# lithium.net
KiCad netlist of a schematic drawn in EAGLE
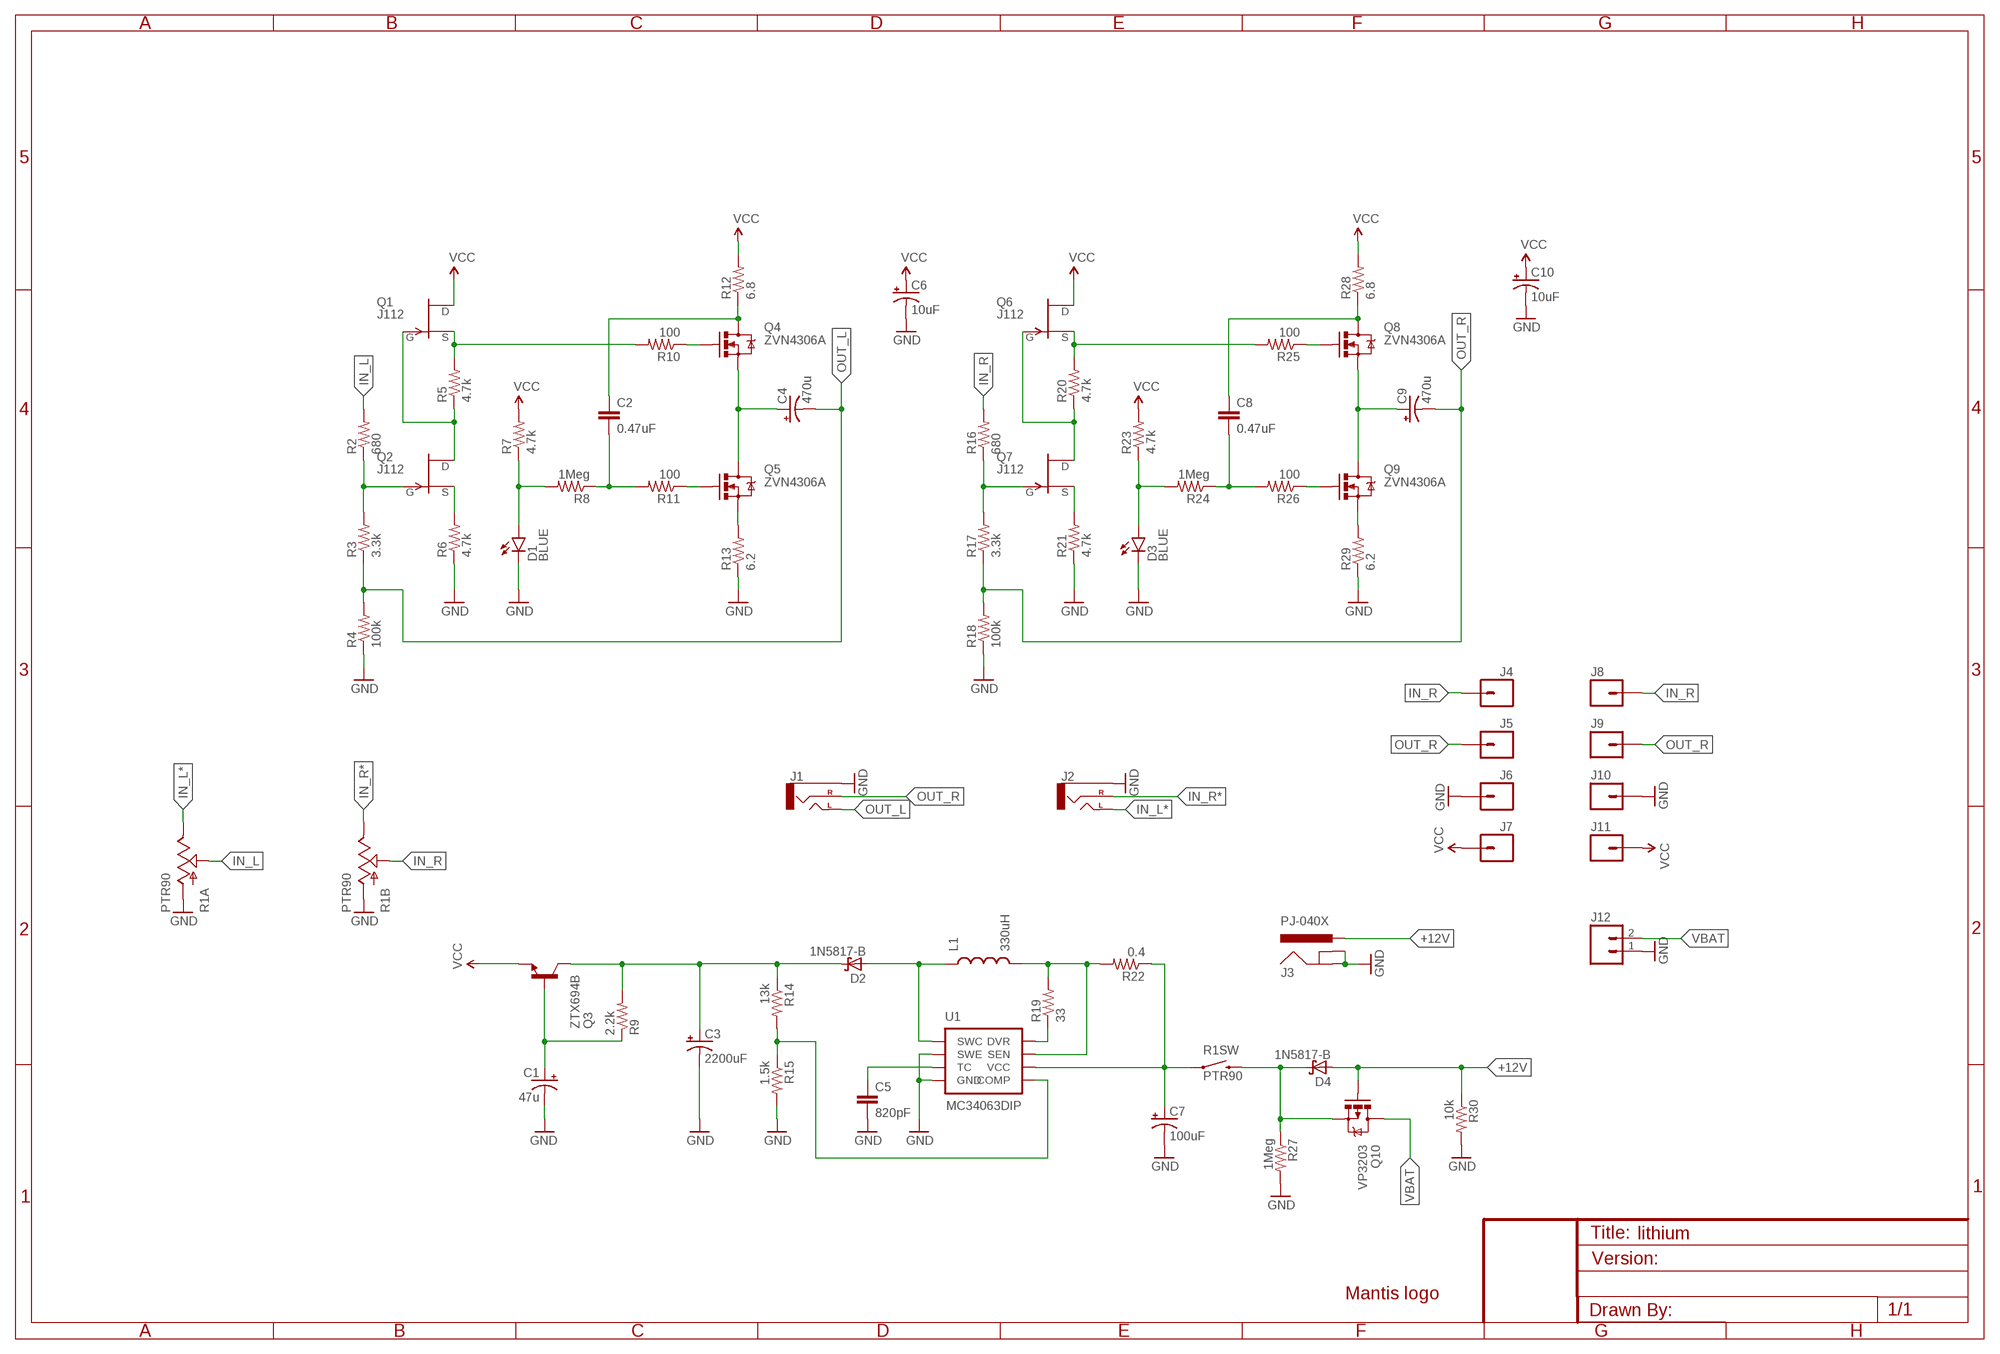
[diagram p0: schematic, sheet 1]

(export (version "E")
  (design (tool "Eeschema 10.0.6"))
  (components
    (comp (ref "C1")
      (value "47u")
      (footprint "eagle-import:CPOL-RADIAL-10UF-25V-SM")
      (libsource (lib "eagle-import") (part "CAP_POLPTH1-SM"))
    )
    (comp (ref "C2")
      (value "0.47uF")
      (footprint "eagle-import:C5B3.5")
      (libsource (lib "eagle-import") (part "C5/3.5"))
    )
    (comp (ref "C3")
      (value "2200uF")
      (footprint "eagle-import:CPOL-RADIAL-1000UF-25V")
      (libsource (lib "eagle-import") (part "CAP_POLPTH4"))
    )
    (comp (ref "C4")
      (value "470u")
      (footprint "eagle-import:CPOL-RADIAL-8_3.5")
      (libsource (lib "eagle-import") (part "CAP_POLPTH8MM"))
    )
    (comp (ref "C5")
      (value "820pF")
      (footprint "eagle-import:CAP-PTH-SMALL")
      (libsource (lib "eagle-import") (part "CAPPTH"))
    )
    (comp (ref "C6")
      (value "10uF")
      (footprint "eagle-import:CPOL-RADIAL-10UF-25V-SM")
      (libsource (lib "eagle-import") (part "CAP_POLPTH1-SM"))
    )
    (comp (ref "C7")
      (value "100uF")
      (footprint "eagle-import:CPOL-RADIAL-100UF-25V")
      (libsource (lib "eagle-import") (part "CAP_POLPTH1"))
    )
    (comp (ref "C8")
      (value "0.47uF")
      (footprint "eagle-import:C5B3.5")
      (libsource (lib "eagle-import") (part "C5/3.5"))
    )
    (comp (ref "C9")
      (value "470u")
      (footprint "eagle-import:CPOL-RADIAL-8_3.5")
      (libsource (lib "eagle-import") (part "CAP_POLPTH8MM"))
    )
    (comp (ref "C10")
      (value "10uF")
      (footprint "eagle-import:CPOL-RADIAL-10UF-25V-SM")
      (libsource (lib "eagle-import") (part "CAP_POLPTH1-SM"))
    )
    (comp (ref "D1")
      (value "BLUE")
      (footprint "eagle-import:LED3MM-SM")
      (libsource (lib "eagle-import") (part "LED3MM-SM"))
    )
    (comp (ref "D2")
      (value "1N5817-B")
      (footprint "eagle-import:DO41-7.6")
      (libsource (lib "eagle-import") (part "1N5817-B"))
    )
    (comp (ref "D3")
      (value "BLUE")
      (footprint "eagle-import:LED3MM-SM")
      (libsource (lib "eagle-import") (part "LED3MM-SM"))
    )
    (comp (ref "D4")
      (value "1N5817-B")
      (footprint "eagle-import:DO41-7.6")
      (libsource (lib "eagle-import") (part "1N5817-B"))
    )
    (comp (ref "J1")
      (value "AUDIO-JACKPTH")
      (footprint "eagle-import:AUDIO-JACK")
      (libsource (lib "eagle-import") (part "AUDIO-JACKPTH"))
    )
    (comp (ref "J2")
      (value "AUDIO-JACKPTH")
      (footprint "eagle-import:AUDIO-JACK")
      (libsource (lib "eagle-import") (part "AUDIO-JACKPTH"))
    )
    (comp (ref "J3")
      (value "PJ-040X")
      (footprint "eagle-import:PJ-040X")
      (libsource (lib "eagle-import") (part "PJ-040X"))
    )
    (comp (ref "J4")
      (value "M01PTH")
      (footprint "eagle-import:1X01")
      (libsource (lib "eagle-import") (part "M01PTH"))
    )
    (comp (ref "J5")
      (value "M01PTH")
      (footprint "eagle-import:1X01")
      (libsource (lib "eagle-import") (part "M01PTH"))
    )
    (comp (ref "J6")
      (value "M01PTH")
      (footprint "eagle-import:1X01")
      (libsource (lib "eagle-import") (part "M01PTH"))
    )
    (comp (ref "J7")
      (value "M01PTH")
      (footprint "eagle-import:1X01")
      (libsource (lib "eagle-import") (part "M01PTH"))
    )
    (comp (ref "J8")
      (value "M01PTH")
      (footprint "eagle-import:1X01")
      (libsource (lib "eagle-import") (part "M01PTH"))
    )
    (comp (ref "J9")
      (value "M01PTH")
      (footprint "eagle-import:1X01")
      (libsource (lib "eagle-import") (part "M01PTH"))
    )
    (comp (ref "J10")
      (value "M01PTH")
      (footprint "eagle-import:1X01")
      (libsource (lib "eagle-import") (part "M01PTH"))
    )
    (comp (ref "J11")
      (value "M01PTH")
      (footprint "eagle-import:1X01")
      (libsource (lib "eagle-import") (part "M01PTH"))
    )
    (comp (ref "J12")
      (value "M02PTH")
      (footprint "eagle-import:1X02")
      (libsource (lib "eagle-import") (part "M02PTH"))
    )
    (comp (ref "L1")
      (value "330uH")
      (footprint "eagle-import:RLB0912")
      (libsource (lib "eagle-import") (part "INDUCTORRLB0912"))
    )
    (comp (ref "LOGO1")
      (value "LOGO-MANTIS")
      (footprint "eagle-import:LOGO-MANTIS")
      (libsource (lib "eagle-import") (part "LOGO-MANTIS"))
    )
    (comp (ref "Q1")
      (value "J112")
      (footprint "eagle-import:TO-92")
      (libsource (lib "eagle-import") (part "J112"))
    )
    (comp (ref "Q2")
      (value "J112")
      (footprint "eagle-import:TO-92")
      (libsource (lib "eagle-import") (part "J112"))
    )
    (comp (ref "Q3")
      (value "ZTX694B")
      (footprint "eagle-import:TO-92")
      (libsource (lib "eagle-import") (part "ZTX694B"))
    )
    (comp (ref "Q4")
      (value "ZVN4306A")
      (footprint "eagle-import:TO-92")
      (libsource (lib "eagle-import") (part "ZVN4306A"))
    )
    (comp (ref "Q5")
      (value "ZVN4306A")
      (footprint "eagle-import:TO-92")
      (libsource (lib "eagle-import") (part "ZVN4306A"))
    )
    (comp (ref "Q6")
      (value "J112")
      (footprint "eagle-import:TO-92")
      (libsource (lib "eagle-import") (part "J112"))
    )
    (comp (ref "Q7")
      (value "J112")
      (footprint "eagle-import:TO-92")
      (libsource (lib "eagle-import") (part "J112"))
    )
    (comp (ref "Q8")
      (value "ZVN4306A")
      (footprint "eagle-import:TO-92")
      (libsource (lib "eagle-import") (part "ZVN4306A"))
    )
    (comp (ref "Q9")
      (value "ZVN4306A")
      (footprint "eagle-import:TO-92")
      (libsource (lib "eagle-import") (part "ZVN4306A"))
    )
    (comp (ref "Q10")
      (value "VP3203")
      (footprint "eagle-import:TO-92")
      (libsource (lib "eagle-import") (part "VP3203"))
    )
    (comp (ref "R1")
      (value "PTR90")
      (footprint "eagle-import:PTR902")
      (libsource (lib "eagle-import") (part "PTR90"))
    )
    (comp (ref "R2")
      (value "680")
      (footprint "eagle-import:AXIAL-0.4-SM")
      (libsource (lib "eagle-import") (part "RESISTORPTH-1/4W-SM"))
    )
    (comp (ref "R3")
      (value "3.3k")
      (footprint "eagle-import:AXIAL-0.4-SM")
      (libsource (lib "eagle-import") (part "RESISTORPTH-1/4W-SM"))
    )
    (comp (ref "R4")
      (value "100k")
      (footprint "eagle-import:AXIAL-0.4-SM")
      (libsource (lib "eagle-import") (part "RESISTORPTH-1/4W-SM"))
    )
    (comp (ref "R5")
      (value "4.7k")
      (footprint "eagle-import:AXIAL-0.4-SM")
      (libsource (lib "eagle-import") (part "RESISTORPTH-1/4W-SM"))
    )
    (comp (ref "R6")
      (value "4.7k")
      (footprint "eagle-import:AXIAL-0.4-SM")
      (libsource (lib "eagle-import") (part "RESISTORPTH-1/4W-SM"))
    )
    (comp (ref "R7")
      (value "4.7k")
      (footprint "eagle-import:AXIAL-0.4-SM")
      (libsource (lib "eagle-import") (part "RESISTORPTH-1/4W-SM"))
    )
    (comp (ref "R8")
      (value "1Meg")
      (footprint "eagle-import:AXIAL-0.4-SM")
      (libsource (lib "eagle-import") (part "RESISTORPTH-1/4W-SM"))
    )
    (comp (ref "R9")
      (value "2.2k")
      (footprint "eagle-import:AXIAL-0.4-SM")
      (libsource (lib "eagle-import") (part "RESISTORPTH-1/4W-SM"))
    )
    (comp (ref "R10")
      (value "100")
      (footprint "eagle-import:AXIAL-0.4-SM")
      (libsource (lib "eagle-import") (part "RESISTORPTH-1/4W-SM"))
    )
    (comp (ref "R11")
      (value "100")
      (footprint "eagle-import:AXIAL-0.4-SM")
      (libsource (lib "eagle-import") (part "RESISTORPTH-1/4W-SM"))
    )
    (comp (ref "R12")
      (value "6.8")
      (footprint "eagle-import:AXIAL-0.4-SM")
      (libsource (lib "eagle-import") (part "RESISTORPTH-1/4W-SM"))
    )
    (comp (ref "R13")
      (value "6.2")
      (footprint "eagle-import:AXIAL-0.4-SM")
      (libsource (lib "eagle-import") (part "RESISTORPTH-1/4W-SM"))
    )
    (comp (ref "R14")
      (value "13k")
      (footprint "eagle-import:AXIAL-0.4-SM")
      (libsource (lib "eagle-import") (part "RESISTORPTH-1/4W-SM"))
    )
    (comp (ref "R15")
      (value "1.5k")
      (footprint "eagle-import:AXIAL-0.4-SM")
      (libsource (lib "eagle-import") (part "RESISTORPTH-1/4W-SM"))
    )
    (comp (ref "R16")
      (value "680")
      (footprint "eagle-import:AXIAL-0.4-SM")
      (libsource (lib "eagle-import") (part "RESISTORPTH-1/4W-SM"))
    )
    (comp (ref "R17")
      (value "3.3k")
      (footprint "eagle-import:AXIAL-0.4-SM")
      (libsource (lib "eagle-import") (part "RESISTORPTH-1/4W-SM"))
    )
    (comp (ref "R18")
      (value "100k")
      (footprint "eagle-import:AXIAL-0.4-SM")
      (libsource (lib "eagle-import") (part "RESISTORPTH-1/4W-SM"))
    )
    (comp (ref "R19")
      (value "33")
      (footprint "eagle-import:AXIAL-0.4-SM")
      (libsource (lib "eagle-import") (part "RESISTORPTH-1/4W-SM"))
    )
    (comp (ref "R20")
      (value "4.7k")
      (footprint "eagle-import:AXIAL-0.4-SM")
      (libsource (lib "eagle-import") (part "RESISTORPTH-1/4W-SM"))
    )
    (comp (ref "R21")
      (value "4.7k")
      (footprint "eagle-import:AXIAL-0.4-SM")
      (libsource (lib "eagle-import") (part "RESISTORPTH-1/4W-SM"))
    )
    (comp (ref "R22")
      (value "0.4")
      (footprint "eagle-import:AXIAL-0.4-SM")
      (libsource (lib "eagle-import") (part "RESISTORPTH-1/4W-SM"))
    )
    (comp (ref "R23")
      (value "4.7k")
      (footprint "eagle-import:AXIAL-0.4-SM")
      (libsource (lib "eagle-import") (part "RESISTORPTH-1/4W-SM"))
    )
    (comp (ref "R24")
      (value "1Meg")
      (footprint "eagle-import:AXIAL-0.4-SM")
      (libsource (lib "eagle-import") (part "RESISTORPTH-1/4W-SM"))
    )
    (comp (ref "R25")
      (value "100")
      (footprint "eagle-import:AXIAL-0.4-SM")
      (libsource (lib "eagle-import") (part "RESISTORPTH-1/4W-SM"))
    )
    (comp (ref "R26")
      (value "100")
      (footprint "eagle-import:AXIAL-0.4-SM")
      (libsource (lib "eagle-import") (part "RESISTORPTH-1/4W-SM"))
    )
    (comp (ref "R27")
      (value "1Meg")
      (footprint "eagle-import:AXIAL-0.4-SM")
      (libsource (lib "eagle-import") (part "RESISTORPTH-1/4W-SM"))
    )
    (comp (ref "R28")
      (value "6.8")
      (footprint "eagle-import:AXIAL-0.4-SM")
      (libsource (lib "eagle-import") (part "RESISTORPTH-1/4W-SM"))
    )
    (comp (ref "R29")
      (value "6.2")
      (footprint "eagle-import:AXIAL-0.4-SM")
      (libsource (lib "eagle-import") (part "RESISTORPTH-1/4W-SM"))
    )
    (comp (ref "R30")
      (value "10k")
      (footprint "eagle-import:AXIAL-0.4-SM")
      (libsource (lib "eagle-import") (part "RESISTORPTH-1/4W-SM"))
    )
    (comp (ref "U1")
      (value "MC34063DIP")
      (footprint "eagle-import:DIP-08")
      (libsource (lib "eagle-import") (part "MC34063DIP"))
    )
  )
  (nets
    (net (code "1") (name "+12V") (class "Default")
      (node (ref "D4") (pin "A") (pinfunction "A_A") (pintype "passive"))
      (node (ref "J3") (pin "1") (pinfunction "PWR_1") (pintype "bidirectional"))
      (node (ref "Q10") (pin "2") (pinfunction "G_2") (pintype "passive"))
      (node (ref "R30") (pin "P$1") (pinfunction "1_P$1") (pintype "passive"))
    )
    (net (code "2") (name "GND") (class "Default")
      (node (ref "C1") (pin "2") (pinfunction "-_2") (pintype "passive"))
      (node (ref "C10") (pin "2") (pinfunction "-_2") (pintype "passive"))
      (node (ref "C3") (pin "-") (pinfunction "-_-") (pintype "passive"))
      (node (ref "C5") (pin "2") (pinfunction "2_2") (pintype "passive"))
      (node (ref "C6") (pin "2") (pinfunction "-_2") (pintype "passive"))
      (node (ref "C7") (pin "2") (pinfunction "-_2") (pintype "passive"))
      (node (ref "D1") (pin "K") (pinfunction "C_K") (pintype "passive"))
      (node (ref "D3") (pin "K") (pinfunction "C_K") (pintype "passive"))
      (node (ref "J1") (pin "SLEEVE") (pinfunction "SLEEVE_SLEEVE") (pintype "bidirectional"))
      (node (ref "J10") (pin "1") (pinfunction "1_1") (pintype "passive"))
      (node (ref "J12") (pin "1") (pinfunction "1_1") (pintype "passive"))
      (node (ref "J2") (pin "SLEEVE") (pinfunction "SLEEVE_SLEEVE") (pintype "bidirectional"))
      (node (ref "J3") (pin "2") (pinfunction "GND_2") (pintype "bidirectional"))
      (node (ref "J3") (pin "3") (pinfunction "GNDBREAK_3") (pintype "bidirectional"))
      (node (ref "J6") (pin "1") (pinfunction "1_1") (pintype "passive"))
      (node (ref "R1") (pin "R1.1") (pinfunction "A_R1.1") (pintype "passive"))
      (node (ref "R1") (pin "R2.1") (pinfunction "A_R2.1") (pintype "passive"))
      (node (ref "R13") (pin "P$1") (pinfunction "1_P$1") (pintype "passive"))
      (node (ref "R15") (pin "P$2") (pinfunction "2_P$2") (pintype "passive"))
      (node (ref "R18") (pin "P$1") (pinfunction "1_P$1") (pintype "passive"))
      (node (ref "R21") (pin "P$1") (pinfunction "1_P$1") (pintype "passive"))
      (node (ref "R27") (pin "P$2") (pinfunction "2_P$2") (pintype "passive"))
      (node (ref "R29") (pin "P$1") (pinfunction "1_P$1") (pintype "passive"))
      (node (ref "R30") (pin "P$2") (pinfunction "2_P$2") (pintype "passive"))
      (node (ref "R4") (pin "P$1") (pinfunction "1_P$1") (pintype "passive"))
      (node (ref "R6") (pin "P$1") (pinfunction "1_P$1") (pintype "passive"))
      (node (ref "U1") (pin "2") (pinfunction "SWE_2") (pintype "bidirectional"))
      (node (ref "U1") (pin "4") (pinfunction "GND_4") (pintype "bidirectional"))
    )
    (net (code "3") (name "IN_L") (class "Default")
      (node (ref "R1") (pin "R1.2") (pinfunction "S_R1.2") (pintype "passive"))
      (node (ref "R2") (pin "P$2") (pinfunction "2_P$2") (pintype "passive"))
    )
    (net (code "4") (name "IN_L*") (class "Default")
      (node (ref "J2") (pin "TIP") (pinfunction "LEFT_TIP") (pintype "bidirectional"))
      (node (ref "R1") (pin "R1.3") (pinfunction "E_R1.3") (pintype "passive"))
    )
    (net (code "5") (name "IN_R") (class "Default")
      (node (ref "J4") (pin "1") (pinfunction "1_1") (pintype "passive"))
      (node (ref "J8") (pin "1") (pinfunction "1_1") (pintype "passive"))
      (node (ref "R1") (pin "R2.2") (pinfunction "S_R2.2") (pintype "passive"))
      (node (ref "R16") (pin "P$2") (pinfunction "2_P$2") (pintype "passive"))
    )
    (net (code "6") (name "IN_R*") (class "Default")
      (node (ref "J2") (pin "RING") (pinfunction "RIGHT_RING") (pintype "bidirectional"))
      (node (ref "R1") (pin "R2.3") (pinfunction "E_R2.3") (pintype "passive"))
    )
    (net (code "7") (name "Net-(C1-+)") (class "Default")
      (node (ref "C1") (pin "1") (pinfunction "+_1") (pintype "passive"))
      (node (ref "Q3") (pin "2") (pinfunction "B_2") (pintype "passive"))
      (node (ref "R9") (pin "P$1") (pinfunction "1_P$1") (pintype "passive"))
    )
    (net (code "8") (name "Net-(C4-+)") (class "Default")
      (node (ref "C4") (pin "1") (pinfunction "+_1") (pintype "passive"))
      (node (ref "Q4") (pin "1") (pinfunction "S_1") (pintype "passive"))
      (node (ref "Q5") (pin "3") (pinfunction "D_3") (pintype "passive"))
    )
    (net (code "9") (name "Net-(C7-+)") (class "Default")
      (node (ref "C7") (pin "1") (pinfunction "+_1") (pintype "passive"))
      (node (ref "R1") (pin "SW1") (pinfunction "1_SW1") (pintype "passive"))
      (node (ref "R22") (pin "P$1") (pinfunction "1_P$1") (pintype "passive"))
      (node (ref "U1") (pin "6") (pinfunction "VCC_6") (pintype "bidirectional"))
    )
    (net (code "10") (name "Net-(C9-+)") (class "Default")
      (node (ref "C9") (pin "1") (pinfunction "+_1") (pintype "passive"))
      (node (ref "Q8") (pin "1") (pinfunction "S_1") (pintype "passive"))
      (node (ref "Q9") (pin "3") (pinfunction "D_3") (pintype "passive"))
    )
    (net (code "11") (name "Net-(Q1-G)") (class "Default")
      (node (ref "Q1") (pin "3") (pinfunction "G_3") (pintype "passive"))
      (node (ref "Q2") (pin "1") (pinfunction "D_1") (pintype "passive"))
      (node (ref "R5") (pin "P$1") (pinfunction "1_P$1") (pintype "passive"))
    )
    (net (code "12") (name "Net-(Q1-S)") (class "Default")
      (node (ref "Q1") (pin "2") (pinfunction "S_2") (pintype "passive"))
      (node (ref "R10") (pin "P$2") (pinfunction "2_P$2") (pintype "passive"))
      (node (ref "R5") (pin "P$2") (pinfunction "2_P$2") (pintype "passive"))
    )
    (net (code "13") (name "Net-(Q2-G)") (class "Default")
      (node (ref "Q2") (pin "3") (pinfunction "G_3") (pintype "passive"))
      (node (ref "R2") (pin "P$1") (pinfunction "1_P$1") (pintype "passive"))
      (node (ref "R3") (pin "P$2") (pinfunction "2_P$2") (pintype "passive"))
    )
    (net (code "14") (name "Net-(Q2-S)") (class "Default")
      (node (ref "Q2") (pin "2") (pinfunction "S_2") (pintype "passive"))
      (node (ref "R6") (pin "P$2") (pinfunction "2_P$2") (pintype "passive"))
    )
    (net (code "15") (name "Net-(Q3-C)") (class "Default")
      (node (ref "C3") (pin "+") (pinfunction "+_+") (pintype "passive"))
      (node (ref "D2") (pin "C") (pinfunction "C_C") (pintype "passive"))
      (node (ref "Q3") (pin "3") (pinfunction "C_3") (pintype "passive"))
      (node (ref "R14") (pin "P$1") (pinfunction "1_P$1") (pintype "passive"))
      (node (ref "R9") (pin "P$2") (pinfunction "2_P$2") (pintype "passive"))
    )
    (net (code "16") (name "Net-(Q4-D)") (class "Default")
      (node (ref "C2") (pin "1") (pinfunction "1_1") (pintype "passive"))
      (node (ref "Q4") (pin "3") (pinfunction "D_3") (pintype "passive"))
      (node (ref "R12") (pin "P$1") (pinfunction "1_P$1") (pintype "passive"))
    )
    (net (code "17") (name "Net-(Q4-G)") (class "Default")
      (node (ref "Q4") (pin "2") (pinfunction "G_2") (pintype "passive"))
      (node (ref "R10") (pin "P$1") (pinfunction "1_P$1") (pintype "passive"))
    )
    (net (code "18") (name "Net-(Q5-G)") (class "Default")
      (node (ref "Q5") (pin "2") (pinfunction "G_2") (pintype "passive"))
      (node (ref "R11") (pin "P$1") (pinfunction "1_P$1") (pintype "passive"))
    )
    (net (code "19") (name "Net-(Q5-S)") (class "Default")
      (node (ref "Q5") (pin "1") (pinfunction "S_1") (pintype "passive"))
      (node (ref "R13") (pin "P$2") (pinfunction "2_P$2") (pintype "passive"))
    )
    (net (code "20") (name "Net-(Q6-G)") (class "Default")
      (node (ref "Q6") (pin "3") (pinfunction "G_3") (pintype "passive"))
      (node (ref "Q7") (pin "1") (pinfunction "D_1") (pintype "passive"))
      (node (ref "R20") (pin "P$1") (pinfunction "1_P$1") (pintype "passive"))
    )
    (net (code "21") (name "Net-(Q6-S)") (class "Default")
      (node (ref "Q6") (pin "2") (pinfunction "S_2") (pintype "passive"))
      (node (ref "R20") (pin "P$2") (pinfunction "2_P$2") (pintype "passive"))
      (node (ref "R25") (pin "P$2") (pinfunction "2_P$2") (pintype "passive"))
    )
    (net (code "22") (name "Net-(Q7-G)") (class "Default")
      (node (ref "Q7") (pin "3") (pinfunction "G_3") (pintype "passive"))
      (node (ref "R16") (pin "P$1") (pinfunction "1_P$1") (pintype "passive"))
      (node (ref "R17") (pin "P$2") (pinfunction "2_P$2") (pintype "passive"))
    )
    (net (code "23") (name "Net-(Q7-S)") (class "Default")
      (node (ref "Q7") (pin "2") (pinfunction "S_2") (pintype "passive"))
      (node (ref "R21") (pin "P$2") (pinfunction "2_P$2") (pintype "passive"))
    )
    (net (code "24") (name "Net-(Q8-D)") (class "Default")
      (node (ref "C8") (pin "1") (pinfunction "1_1") (pintype "passive"))
      (node (ref "Q8") (pin "3") (pinfunction "D_3") (pintype "passive"))
      (node (ref "R28") (pin "P$1") (pinfunction "1_P$1") (pintype "passive"))
    )
    (net (code "25") (name "Net-(Q8-G)") (class "Default")
      (node (ref "Q8") (pin "2") (pinfunction "G_2") (pintype "passive"))
      (node (ref "R25") (pin "P$1") (pinfunction "1_P$1") (pintype "passive"))
    )
    (net (code "26") (name "Net-(Q9-G)") (class "Default")
      (node (ref "Q9") (pin "2") (pinfunction "G_2") (pintype "passive"))
      (node (ref "R26") (pin "P$1") (pinfunction "1_P$1") (pintype "passive"))
    )
    (net (code "27") (name "Net-(Q9-S)") (class "Default")
      (node (ref "Q9") (pin "1") (pinfunction "S_1") (pintype "passive"))
      (node (ref "R29") (pin "P$2") (pinfunction "2_P$2") (pintype "passive"))
    )
    (net (code "28") (name "Net-(Q10-S)") (class "Default")
      (node (ref "D4") (pin "C") (pinfunction "C_C") (pintype "passive"))
      (node (ref "Q10") (pin "1") (pinfunction "S_1") (pintype "passive"))
      (node (ref "R1") (pin "SW2") (pinfunction "2_SW2") (pintype "passive"))
      (node (ref "R27") (pin "P$1") (pinfunction "1_P$1") (pintype "passive"))
    )
    (net (code "29") (name "Net-(R7-1)") (class "Default")
      (node (ref "D1") (pin "A") (pinfunction "A_A") (pintype "passive"))
      (node (ref "R7") (pin "P$1") (pinfunction "1_P$1") (pintype "passive"))
      (node (ref "R8") (pin "P$2") (pinfunction "2_P$2") (pintype "passive"))
    )
    (net (code "30") (name "Net-(R11-2)") (class "Default")
      (node (ref "C2") (pin "2") (pinfunction "2_2") (pintype "passive"))
      (node (ref "R11") (pin "P$2") (pinfunction "2_P$2") (pintype "passive"))
      (node (ref "R8") (pin "P$1") (pinfunction "1_P$1") (pintype "passive"))
    )
    (net (code "31") (name "Net-(R14-2)") (class "Default")
      (node (ref "R14") (pin "P$2") (pinfunction "2_P$2") (pintype "passive"))
      (node (ref "R15") (pin "P$1") (pinfunction "1_P$1") (pintype "passive"))
      (node (ref "U1") (pin "5") (pinfunction "COMP_5") (pintype "bidirectional"))
    )
    (net (code "32") (name "Net-(R19-1)") (class "Default")
      (node (ref "R19") (pin "P$1") (pinfunction "1_P$1") (pintype "passive"))
      (node (ref "U1") (pin "8") (pinfunction "DVR_8") (pintype "bidirectional"))
    )
    (net (code "33") (name "Net-(R19-2)") (class "Default")
      (node (ref "L1") (pin "2") (pinfunction "2_2") (pintype "passive"))
      (node (ref "R19") (pin "P$2") (pinfunction "2_P$2") (pintype "passive"))
      (node (ref "R22") (pin "P$2") (pinfunction "2_P$2") (pintype "passive"))
      (node (ref "U1") (pin "7") (pinfunction "SEN_7") (pintype "bidirectional"))
    )
    (net (code "34") (name "Net-(R23-1)") (class "Default")
      (node (ref "D3") (pin "A") (pinfunction "A_A") (pintype "passive"))
      (node (ref "R23") (pin "P$1") (pinfunction "1_P$1") (pintype "passive"))
      (node (ref "R24") (pin "P$2") (pinfunction "2_P$2") (pintype "passive"))
    )
    (net (code "35") (name "Net-(R24-1)") (class "Default")
      (node (ref "C8") (pin "2") (pinfunction "2_2") (pintype "passive"))
      (node (ref "R24") (pin "P$1") (pinfunction "1_P$1") (pintype "passive"))
      (node (ref "R26") (pin "P$2") (pinfunction "2_P$2") (pintype "passive"))
    )
    (net (code "36") (name "Net-(U1-SWC)") (class "Default")
      (node (ref "D2") (pin "A") (pinfunction "A_A") (pintype "passive"))
      (node (ref "L1") (pin "1") (pinfunction "1_1") (pintype "passive"))
      (node (ref "U1") (pin "1") (pinfunction "SWC_1") (pintype "bidirectional"))
    )
    (net (code "37") (name "Net-(U1-TC)") (class "Default")
      (node (ref "C5") (pin "1") (pinfunction "1_1") (pintype "passive"))
      (node (ref "U1") (pin "3") (pinfunction "TC_3") (pintype "bidirectional"))
    )
    (net (code "38") (name "OUT_L") (class "Default")
      (node (ref "C4") (pin "2") (pinfunction "-_2") (pintype "passive"))
      (node (ref "J1") (pin "TIP") (pinfunction "LEFT_TIP") (pintype "bidirectional"))
      (node (ref "R3") (pin "P$1") (pinfunction "1_P$1") (pintype "passive"))
      (node (ref "R4") (pin "P$2") (pinfunction "2_P$2") (pintype "passive"))
    )
    (net (code "39") (name "OUT_R") (class "Default")
      (node (ref "C9") (pin "2") (pinfunction "-_2") (pintype "passive"))
      (node (ref "J1") (pin "RING") (pinfunction "RIGHT_RING") (pintype "bidirectional"))
      (node (ref "J5") (pin "1") (pinfunction "1_1") (pintype "passive"))
      (node (ref "J9") (pin "1") (pinfunction "1_1") (pintype "passive"))
      (node (ref "R17") (pin "P$1") (pinfunction "1_P$1") (pintype "passive"))
      (node (ref "R18") (pin "P$2") (pinfunction "2_P$2") (pintype "passive"))
    )
    (net (code "40") (name "VBAT") (class "Default")
      (node (ref "J12") (pin "2") (pinfunction "2_2") (pintype "passive"))
      (node (ref "Q10") (pin "3") (pinfunction "D_3") (pintype "passive"))
    )
    (net (code "41") (name "VCC") (class "Default")
      (node (ref "C10") (pin "1") (pinfunction "+_1") (pintype "passive"))
      (node (ref "C6") (pin "1") (pinfunction "+_1") (pintype "passive"))
      (node (ref "J11") (pin "1") (pinfunction "1_1") (pintype "passive"))
      (node (ref "J7") (pin "1") (pinfunction "1_1") (pintype "passive"))
      (node (ref "Q1") (pin "1") (pinfunction "D_1") (pintype "passive"))
      (node (ref "Q3") (pin "1") (pinfunction "E_1") (pintype "passive"))
      (node (ref "Q6") (pin "1") (pinfunction "D_1") (pintype "passive"))
      (node (ref "R12") (pin "P$2") (pinfunction "2_P$2") (pintype "passive"))
      (node (ref "R23") (pin "P$2") (pinfunction "2_P$2") (pintype "passive"))
      (node (ref "R28") (pin "P$2") (pinfunction "2_P$2") (pintype "passive"))
      (node (ref "R7") (pin "P$2") (pinfunction "2_P$2") (pintype "passive"))
    )
  )
)
